# S6-EXP-Bridge.net
KiCad netlist of a schematic drawn in Altium Designer
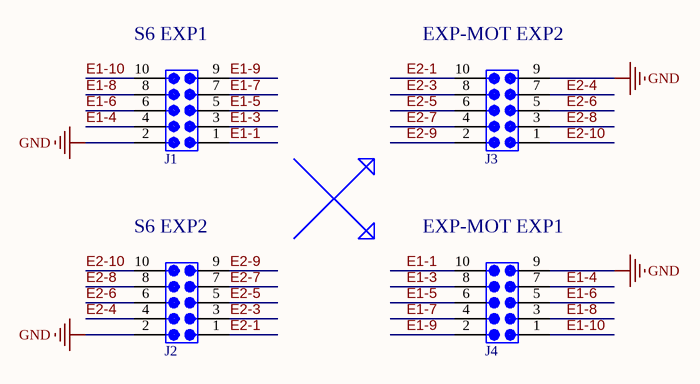
[diagram p0: S6-EXP-Bridge.SchDoc]

(export (version "E")
  (design (tool "Eeschema 10.0.6"))
  (components
    (comp (ref "J1")
      (value "SFH11-PBPC-D05-ST-BK")
      (footprint "R2X5")
      (description "2x5 2.54mm Pin Receptacle")
      (libsource (lib "MbientLab") (part "R100_2x5"))
    )
    (comp (ref "J2")
      (value "SFH11-PBPC-D05-ST-BK")
      (footprint "R2X5")
      (description "2x5 2.54mm Pin Receptacle")
      (libsource (lib "MbientLab") (part "R100_2x5"))
    )
    (comp (ref "J3")
      (value "SFH11-PBPC-D05-ST-BK")
      (footprint "R2X5")
      (description "2x5 2.54mm Pin Receptacle")
      (libsource (lib "MbientLab") (part "R100_2x5"))
    )
    (comp (ref "J4")
      (value "SFH11-PBPC-D05-ST-BK")
      (footprint "R2X5")
      (description "2x5 2.54mm Pin Receptacle")
      (libsource (lib "MbientLab") (part "R100_2x5"))
    )
  )
  (nets
    (net (code "1") (name "/E1-1") (class "Default")
      (node (ref "J1") (pin "1") (pinfunction "1_1") (pintype "passive"))
      (node (ref "J4") (pin "10") (pinfunction "10_10") (pintype "passive"))
    )
    (net (code "2") (name "/E1-3") (class "Default")
      (node (ref "J1") (pin "3") (pinfunction "3_3") (pintype "passive"))
      (node (ref "J4") (pin "8") (pinfunction "8_8") (pintype "passive"))
    )
    (net (code "3") (name "/E1-4") (class "Default")
      (node (ref "J1") (pin "4") (pinfunction "4_4") (pintype "passive"))
      (node (ref "J4") (pin "7") (pinfunction "7_7") (pintype "passive"))
    )
    (net (code "4") (name "/E1-5") (class "Default")
      (node (ref "J1") (pin "5") (pinfunction "5_5") (pintype "passive"))
      (node (ref "J4") (pin "6") (pinfunction "6_6") (pintype "passive"))
    )
    (net (code "5") (name "/E1-6") (class "Default")
      (node (ref "J1") (pin "6") (pinfunction "6_6") (pintype "passive"))
      (node (ref "J4") (pin "5") (pinfunction "5_5") (pintype "passive"))
    )
    (net (code "6") (name "/E1-7") (class "Default")
      (node (ref "J1") (pin "7") (pinfunction "7_7") (pintype "passive"))
      (node (ref "J4") (pin "4") (pinfunction "4_4") (pintype "passive"))
    )
    (net (code "7") (name "/E1-8") (class "Default")
      (node (ref "J1") (pin "8") (pinfunction "8_8") (pintype "passive"))
      (node (ref "J4") (pin "3") (pinfunction "3_3") (pintype "passive"))
    )
    (net (code "8") (name "/E1-9") (class "Default")
      (node (ref "J1") (pin "9") (pinfunction "9_9") (pintype "passive"))
      (node (ref "J4") (pin "2") (pinfunction "2_2") (pintype "passive"))
    )
    (net (code "9") (name "/E1-10") (class "Default")
      (node (ref "J1") (pin "10") (pinfunction "10_10") (pintype "passive"))
      (node (ref "J4") (pin "1") (pinfunction "1_1") (pintype "passive"))
    )
    (net (code "10") (name "/E2-1") (class "Default")
      (node (ref "J2") (pin "1") (pinfunction "1_1") (pintype "passive"))
      (node (ref "J3") (pin "10") (pinfunction "10_10") (pintype "passive"))
    )
    (net (code "11") (name "/E2-3") (class "Default")
      (node (ref "J2") (pin "3") (pinfunction "3_3") (pintype "passive"))
      (node (ref "J3") (pin "8") (pinfunction "8_8") (pintype "passive"))
    )
    (net (code "12") (name "/E2-4") (class "Default")
      (node (ref "J2") (pin "4") (pinfunction "4_4") (pintype "passive"))
      (node (ref "J3") (pin "7") (pinfunction "7_7") (pintype "passive"))
    )
    (net (code "13") (name "/E2-5") (class "Default")
      (node (ref "J2") (pin "5") (pinfunction "5_5") (pintype "passive"))
      (node (ref "J3") (pin "6") (pinfunction "6_6") (pintype "passive"))
    )
    (net (code "14") (name "/E2-6") (class "Default")
      (node (ref "J2") (pin "6") (pinfunction "6_6") (pintype "passive"))
      (node (ref "J3") (pin "5") (pinfunction "5_5") (pintype "passive"))
    )
    (net (code "15") (name "/E2-7") (class "Default")
      (node (ref "J2") (pin "7") (pinfunction "7_7") (pintype "passive"))
      (node (ref "J3") (pin "4") (pinfunction "4_4") (pintype "passive"))
    )
    (net (code "16") (name "/E2-8") (class "Default")
      (node (ref "J2") (pin "8") (pinfunction "8_8") (pintype "passive"))
      (node (ref "J3") (pin "3") (pinfunction "3_3") (pintype "passive"))
    )
    (net (code "17") (name "/E2-9") (class "Default")
      (node (ref "J2") (pin "9") (pinfunction "9_9") (pintype "passive"))
      (node (ref "J3") (pin "2") (pinfunction "2_2") (pintype "passive"))
    )
    (net (code "18") (name "/E2-10") (class "Default")
      (node (ref "J2") (pin "10") (pinfunction "10_10") (pintype "passive"))
      (node (ref "J3") (pin "1") (pinfunction "1_1") (pintype "passive"))
    )
    (net (code "19") (name "GND") (class "Default")
      (node (ref "J1") (pin "2") (pinfunction "2_2") (pintype "passive"))
      (node (ref "J2") (pin "2") (pinfunction "2_2") (pintype "passive"))
      (node (ref "J3") (pin "9") (pinfunction "9_9") (pintype "passive"))
      (node (ref "J4") (pin "9") (pinfunction "9_9") (pintype "passive"))
    )
  )
)
